# M141B.net
KiCad netlist of a schematic drawn in EAGLE
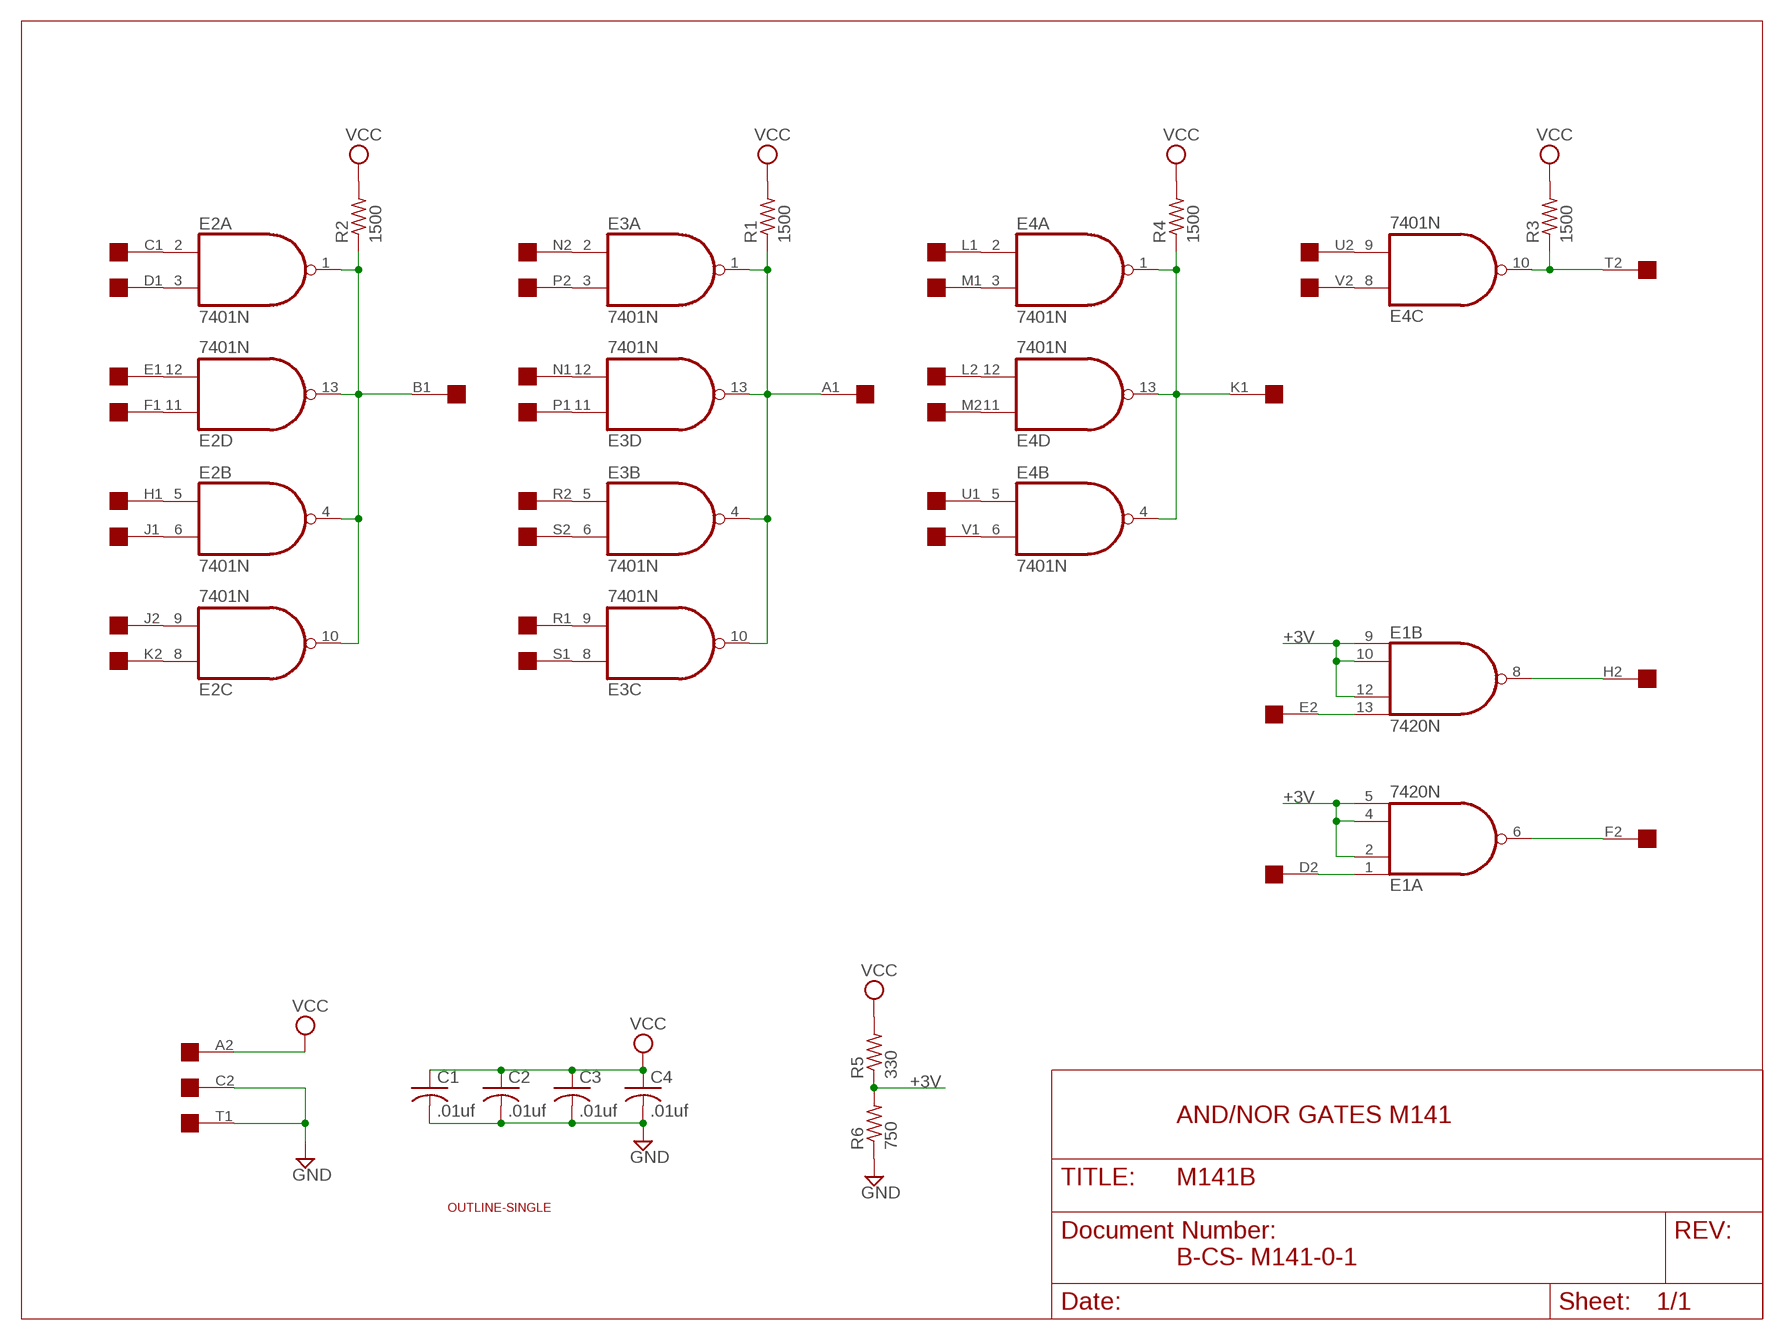
[diagram p0: schematic, sheet 1]

(export (version "E")
  (design (tool "Eeschema 10.0.6"))
  (components
    (comp (ref "C1")
      (value ".01uf")
      (footprint "eagle-import:C050-025X075")
      (libsource (lib "eagle-import") (part "C-US050-025X075"))
    )
    (comp (ref "C2")
      (value ".01uf")
      (footprint "eagle-import:C050-025X075")
      (libsource (lib "eagle-import") (part "C-US050-025X075"))
    )
    (comp (ref "C3")
      (value ".01uf")
      (footprint "eagle-import:C050-025X075")
      (libsource (lib "eagle-import") (part "C-US050-025X075"))
    )
    (comp (ref "C4")
      (value ".01uf")
      (footprint "eagle-import:C050-025X075")
      (libsource (lib "eagle-import") (part "C-US050-025X075"))
    )
    (comp (ref "E1")
      (value "7420N")
      (footprint "eagle-import:DIL14")
      (libsource (lib "eagle-import") (part "7420NS"))
    )
    (comp (ref "E2")
      (value "7401N")
      (footprint "eagle-import:DIL14")
      (libsource (lib "eagle-import") (part "7401NLS"))
    )
    (comp (ref "E3")
      (value "7401N")
      (footprint "eagle-import:DIL14")
      (libsource (lib "eagle-import") (part "7401NLS"))
    )
    (comp (ref "E4")
      (value "7401N")
      (footprint "eagle-import:DIL14")
      (libsource (lib "eagle-import") (part "7401NLS"))
    )
    (comp (ref "R1")
      (value "1500")
      (footprint "eagle-import:0207_10")
      (libsource (lib "eagle-import") (part "R-US_0207/10"))
    )
    (comp (ref "R2")
      (value "1500")
      (footprint "eagle-import:0207_10")
      (libsource (lib "eagle-import") (part "R-US_0207/10"))
    )
    (comp (ref "R3")
      (value "1500")
      (footprint "eagle-import:0207_10")
      (libsource (lib "eagle-import") (part "R-US_0207/10"))
    )
    (comp (ref "R4")
      (value "1500")
      (footprint "eagle-import:0207_10")
      (libsource (lib "eagle-import") (part "R-US_0207/10"))
    )
    (comp (ref "R5")
      (value "330")
      (footprint "eagle-import:0207_10")
      (libsource (lib "eagle-import") (part "R-US_0207/10"))
    )
    (comp (ref "R6")
      (value "750")
      (footprint "eagle-import:0207_10")
      (libsource (lib "eagle-import") (part "R-US_0207/10"))
    )
    (comp (ref "U$1")
      (value "OUTLINE-SINGLE")
      (footprint "eagle-import:SINGLE")
      (libsource (lib "eagle-import") (part "OUTLINE-SINGLE"))
    )
    (comp (ref "U$4")
      (value "SINGLE")
      (footprint "eagle-import:EDGE-CON2")
      (libsource (lib "eagle-import") (part "SINGLE"))
    )
  )
  (nets
    (net (code "1") (name "/+3V") (class "Default")
      (node (ref "E1") (pin "10") (pinfunction "I1_10") (pintype "input"))
      (node (ref "E1") (pin "12") (pinfunction "I2_12") (pintype "input"))
      (node (ref "E1") (pin "2") (pinfunction "I1_2") (pintype "input"))
      (node (ref "E1") (pin "4") (pinfunction "I2_4") (pintype "input"))
      (node (ref "E1") (pin "5") (pinfunction "I3_5") (pintype "input"))
      (node (ref "E1") (pin "9") (pinfunction "I0_9") (pintype "input"))
      (node (ref "R5") (pin "1") (pinfunction "1_1") (pintype "passive"))
      (node (ref "R6") (pin "2") (pinfunction "2_2") (pintype "passive"))
    )
    (net (code "2") (name "GND") (class "Default")
      (node (ref "C1") (pin "2") (pinfunction "2_2") (pintype "passive"))
      (node (ref "C2") (pin "2") (pinfunction "2_2") (pintype "passive"))
      (node (ref "C3") (pin "2") (pinfunction "2_2") (pintype "passive"))
      (node (ref "C4") (pin "2") (pinfunction "2_2") (pintype "passive"))
      (node (ref "R6") (pin "1") (pinfunction "1_1") (pintype "passive"))
      (node (ref "U$4") (pin "C2") (pinfunction "1_C2") (pintype "bidirectional"))
      (node (ref "U$4") (pin "T1") (pinfunction "1_T1") (pintype "bidirectional"))
    )
    (net (code "3") (name "Net-(E1A-I0)") (class "Default")
      (node (ref "E1") (pin "1") (pinfunction "I0_1") (pintype "input"))
      (node (ref "U$4") (pin "D2") (pinfunction "1_D2") (pintype "bidirectional"))
    )
    (net (code "4") (name "Net-(E1A-O)") (class "Default")
      (node (ref "E1") (pin "6") (pinfunction "O_6") (pintype "output"))
      (node (ref "U$4") (pin "F2") (pinfunction "1_F2") (pintype "bidirectional"))
    )
    (net (code "5") (name "Net-(E1B-I3)") (class "Default")
      (node (ref "E1") (pin "13") (pinfunction "I3_13") (pintype "input"))
      (node (ref "U$4") (pin "E2") (pinfunction "1_E2") (pintype "bidirectional"))
    )
    (net (code "6") (name "Net-(E1B-O)") (class "Default")
      (node (ref "E1") (pin "8") (pinfunction "O_8") (pintype "output"))
      (node (ref "U$4") (pin "H2") (pinfunction "1_H2") (pintype "bidirectional"))
    )
    (net (code "7") (name "Net-(E2A-I0)") (class "Default")
      (node (ref "E2") (pin "2") (pinfunction "I0_2") (pintype "input"))
      (node (ref "U$4") (pin "C1") (pinfunction "1_C1") (pintype "bidirectional"))
    )
    (net (code "8") (name "Net-(E2A-I1)") (class "Default")
      (node (ref "E2") (pin "3") (pinfunction "I1_3") (pintype "input"))
      (node (ref "U$4") (pin "D1") (pinfunction "1_D1") (pintype "bidirectional"))
    )
    (net (code "9") (name "Net-(E2A-O)") (class "Default")
      (node (ref "E2") (pin "1") (pinfunction "O_1") (pintype "open_collector"))
      (node (ref "E2") (pin "10") (pinfunction "O_10") (pintype "open_collector"))
      (node (ref "E2") (pin "13") (pinfunction "O_13") (pintype "open_collector"))
      (node (ref "E2") (pin "4") (pinfunction "O_4") (pintype "open_collector"))
      (node (ref "R2") (pin "1") (pinfunction "1_1") (pintype "passive"))
      (node (ref "U$4") (pin "B1") (pinfunction "1_B1") (pintype "bidirectional"))
    )
    (net (code "10") (name "Net-(E2B-I0)") (class "Default")
      (node (ref "E2") (pin "5") (pinfunction "I0_5") (pintype "input"))
      (node (ref "U$4") (pin "H1") (pinfunction "1_H1") (pintype "bidirectional"))
    )
    (net (code "11") (name "Net-(E2B-I1)") (class "Default")
      (node (ref "E2") (pin "6") (pinfunction "I1_6") (pintype "input"))
      (node (ref "U$4") (pin "J1") (pinfunction "1_J1") (pintype "bidirectional"))
    )
    (net (code "12") (name "Net-(E2C-I0)") (class "Default")
      (node (ref "E2") (pin "8") (pinfunction "I0_8") (pintype "input"))
      (node (ref "U$4") (pin "K2") (pinfunction "1_K2") (pintype "bidirectional"))
    )
    (net (code "13") (name "Net-(E2C-I1)") (class "Default")
      (node (ref "E2") (pin "9") (pinfunction "I1_9") (pintype "input"))
      (node (ref "U$4") (pin "J2") (pinfunction "1_J2") (pintype "bidirectional"))
    )
    (net (code "14") (name "Net-(E2D-I0)") (class "Default")
      (node (ref "E2") (pin "11") (pinfunction "I0_11") (pintype "input"))
      (node (ref "U$4") (pin "F1") (pinfunction "1_F1") (pintype "bidirectional"))
    )
    (net (code "15") (name "Net-(E2D-I1)") (class "Default")
      (node (ref "E2") (pin "12") (pinfunction "I1_12") (pintype "input"))
      (node (ref "U$4") (pin "E1") (pinfunction "1_E1") (pintype "bidirectional"))
    )
    (net (code "16") (name "Net-(E3A-I0)") (class "Default")
      (node (ref "E3") (pin "2") (pinfunction "I0_2") (pintype "input"))
      (node (ref "U$4") (pin "N2") (pinfunction "1_N2") (pintype "bidirectional"))
    )
    (net (code "17") (name "Net-(E3A-I1)") (class "Default")
      (node (ref "E3") (pin "3") (pinfunction "I1_3") (pintype "input"))
      (node (ref "U$4") (pin "P2") (pinfunction "1_P2") (pintype "bidirectional"))
    )
    (net (code "18") (name "Net-(E3A-O)") (class "Default")
      (node (ref "E3") (pin "1") (pinfunction "O_1") (pintype "open_collector"))
      (node (ref "E3") (pin "10") (pinfunction "O_10") (pintype "open_collector"))
      (node (ref "E3") (pin "13") (pinfunction "O_13") (pintype "open_collector"))
      (node (ref "E3") (pin "4") (pinfunction "O_4") (pintype "open_collector"))
      (node (ref "R1") (pin "1") (pinfunction "1_1") (pintype "passive"))
      (node (ref "U$4") (pin "A1") (pinfunction "1_A1") (pintype "bidirectional"))
    )
    (net (code "19") (name "Net-(E3B-I0)") (class "Default")
      (node (ref "E3") (pin "5") (pinfunction "I0_5") (pintype "input"))
      (node (ref "U$4") (pin "R2") (pinfunction "1_R2") (pintype "bidirectional"))
    )
    (net (code "20") (name "Net-(E3B-I1)") (class "Default")
      (node (ref "E3") (pin "6") (pinfunction "I1_6") (pintype "input"))
      (node (ref "U$4") (pin "S2") (pinfunction "1_S2") (pintype "bidirectional"))
    )
    (net (code "21") (name "Net-(E3C-I0)") (class "Default")
      (node (ref "E3") (pin "8") (pinfunction "I0_8") (pintype "input"))
      (node (ref "U$4") (pin "S1") (pinfunction "1_S1") (pintype "bidirectional"))
    )
    (net (code "22") (name "Net-(E3C-I1)") (class "Default")
      (node (ref "E3") (pin "9") (pinfunction "I1_9") (pintype "input"))
      (node (ref "U$4") (pin "R1") (pinfunction "1_R1") (pintype "bidirectional"))
    )
    (net (code "23") (name "Net-(E3D-I0)") (class "Default")
      (node (ref "E3") (pin "11") (pinfunction "I0_11") (pintype "input"))
      (node (ref "U$4") (pin "P1") (pinfunction "1_P1") (pintype "bidirectional"))
    )
    (net (code "24") (name "Net-(E3D-I1)") (class "Default")
      (node (ref "E3") (pin "12") (pinfunction "I1_12") (pintype "input"))
      (node (ref "U$4") (pin "N1") (pinfunction "1_N1") (pintype "bidirectional"))
    )
    (net (code "25") (name "Net-(E4A-I0)") (class "Default")
      (node (ref "E4") (pin "2") (pinfunction "I0_2") (pintype "input"))
      (node (ref "U$4") (pin "L1") (pinfunction "1_L1") (pintype "bidirectional"))
    )
    (net (code "26") (name "Net-(E4A-I1)") (class "Default")
      (node (ref "E4") (pin "3") (pinfunction "I1_3") (pintype "input"))
      (node (ref "U$4") (pin "M1") (pinfunction "1_M1") (pintype "bidirectional"))
    )
    (net (code "27") (name "Net-(E4A-O)") (class "Default")
      (node (ref "E4") (pin "1") (pinfunction "O_1") (pintype "open_collector"))
      (node (ref "E4") (pin "13") (pinfunction "O_13") (pintype "open_collector"))
      (node (ref "E4") (pin "4") (pinfunction "O_4") (pintype "open_collector"))
      (node (ref "R4") (pin "1") (pinfunction "1_1") (pintype "passive"))
      (node (ref "U$4") (pin "K1") (pinfunction "1_K1") (pintype "bidirectional"))
    )
    (net (code "28") (name "Net-(E4B-I0)") (class "Default")
      (node (ref "E4") (pin "5") (pinfunction "I0_5") (pintype "input"))
      (node (ref "U$4") (pin "U1") (pinfunction "1_U1") (pintype "bidirectional"))
    )
    (net (code "29") (name "Net-(E4B-I1)") (class "Default")
      (node (ref "E4") (pin "6") (pinfunction "I1_6") (pintype "input"))
      (node (ref "U$4") (pin "V1") (pinfunction "1_V1") (pintype "bidirectional"))
    )
    (net (code "30") (name "Net-(E4C-I0)") (class "Default")
      (node (ref "E4") (pin "8") (pinfunction "I0_8") (pintype "input"))
      (node (ref "U$4") (pin "V2") (pinfunction "1_V2") (pintype "bidirectional"))
    )
    (net (code "31") (name "Net-(E4C-I1)") (class "Default")
      (node (ref "E4") (pin "9") (pinfunction "I1_9") (pintype "input"))
      (node (ref "U$4") (pin "U2") (pinfunction "1_U2") (pintype "bidirectional"))
    )
    (net (code "32") (name "Net-(E4C-O)") (class "Default")
      (node (ref "E4") (pin "10") (pinfunction "O_10") (pintype "open_collector"))
      (node (ref "R3") (pin "1") (pinfunction "1_1") (pintype "passive"))
      (node (ref "U$4") (pin "T2") (pinfunction "1_T2") (pintype "bidirectional"))
    )
    (net (code "33") (name "Net-(E4D-I0)") (class "Default")
      (node (ref "E4") (pin "11") (pinfunction "I0_11") (pintype "input"))
      (node (ref "U$4") (pin "M2") (pinfunction "1_M2") (pintype "bidirectional"))
    )
    (net (code "34") (name "Net-(E4D-I1)") (class "Default")
      (node (ref "E4") (pin "12") (pinfunction "I1_12") (pintype "input"))
      (node (ref "U$4") (pin "L2") (pinfunction "1_L2") (pintype "bidirectional"))
    )
    (net (code "35") (name "VCC") (class "Default")
      (node (ref "C1") (pin "1") (pinfunction "1_1") (pintype "passive"))
      (node (ref "C2") (pin "1") (pinfunction "1_1") (pintype "passive"))
      (node (ref "C3") (pin "1") (pinfunction "1_1") (pintype "passive"))
      (node (ref "C4") (pin "1") (pinfunction "1_1") (pintype "passive"))
      (node (ref "R1") (pin "2") (pinfunction "2_2") (pintype "passive"))
      (node (ref "R2") (pin "2") (pinfunction "2_2") (pintype "passive"))
      (node (ref "R3") (pin "2") (pinfunction "2_2") (pintype "passive"))
      (node (ref "R4") (pin "2") (pinfunction "2_2") (pintype "passive"))
      (node (ref "R5") (pin "2") (pinfunction "2_2") (pintype "passive"))
      (node (ref "U$4") (pin "A2") (pinfunction "1_A2") (pintype "bidirectional"))
    )
  )
)
